# LedGameboardLamp.net
KiCad netlist of a schematic drawn in EasyEDA
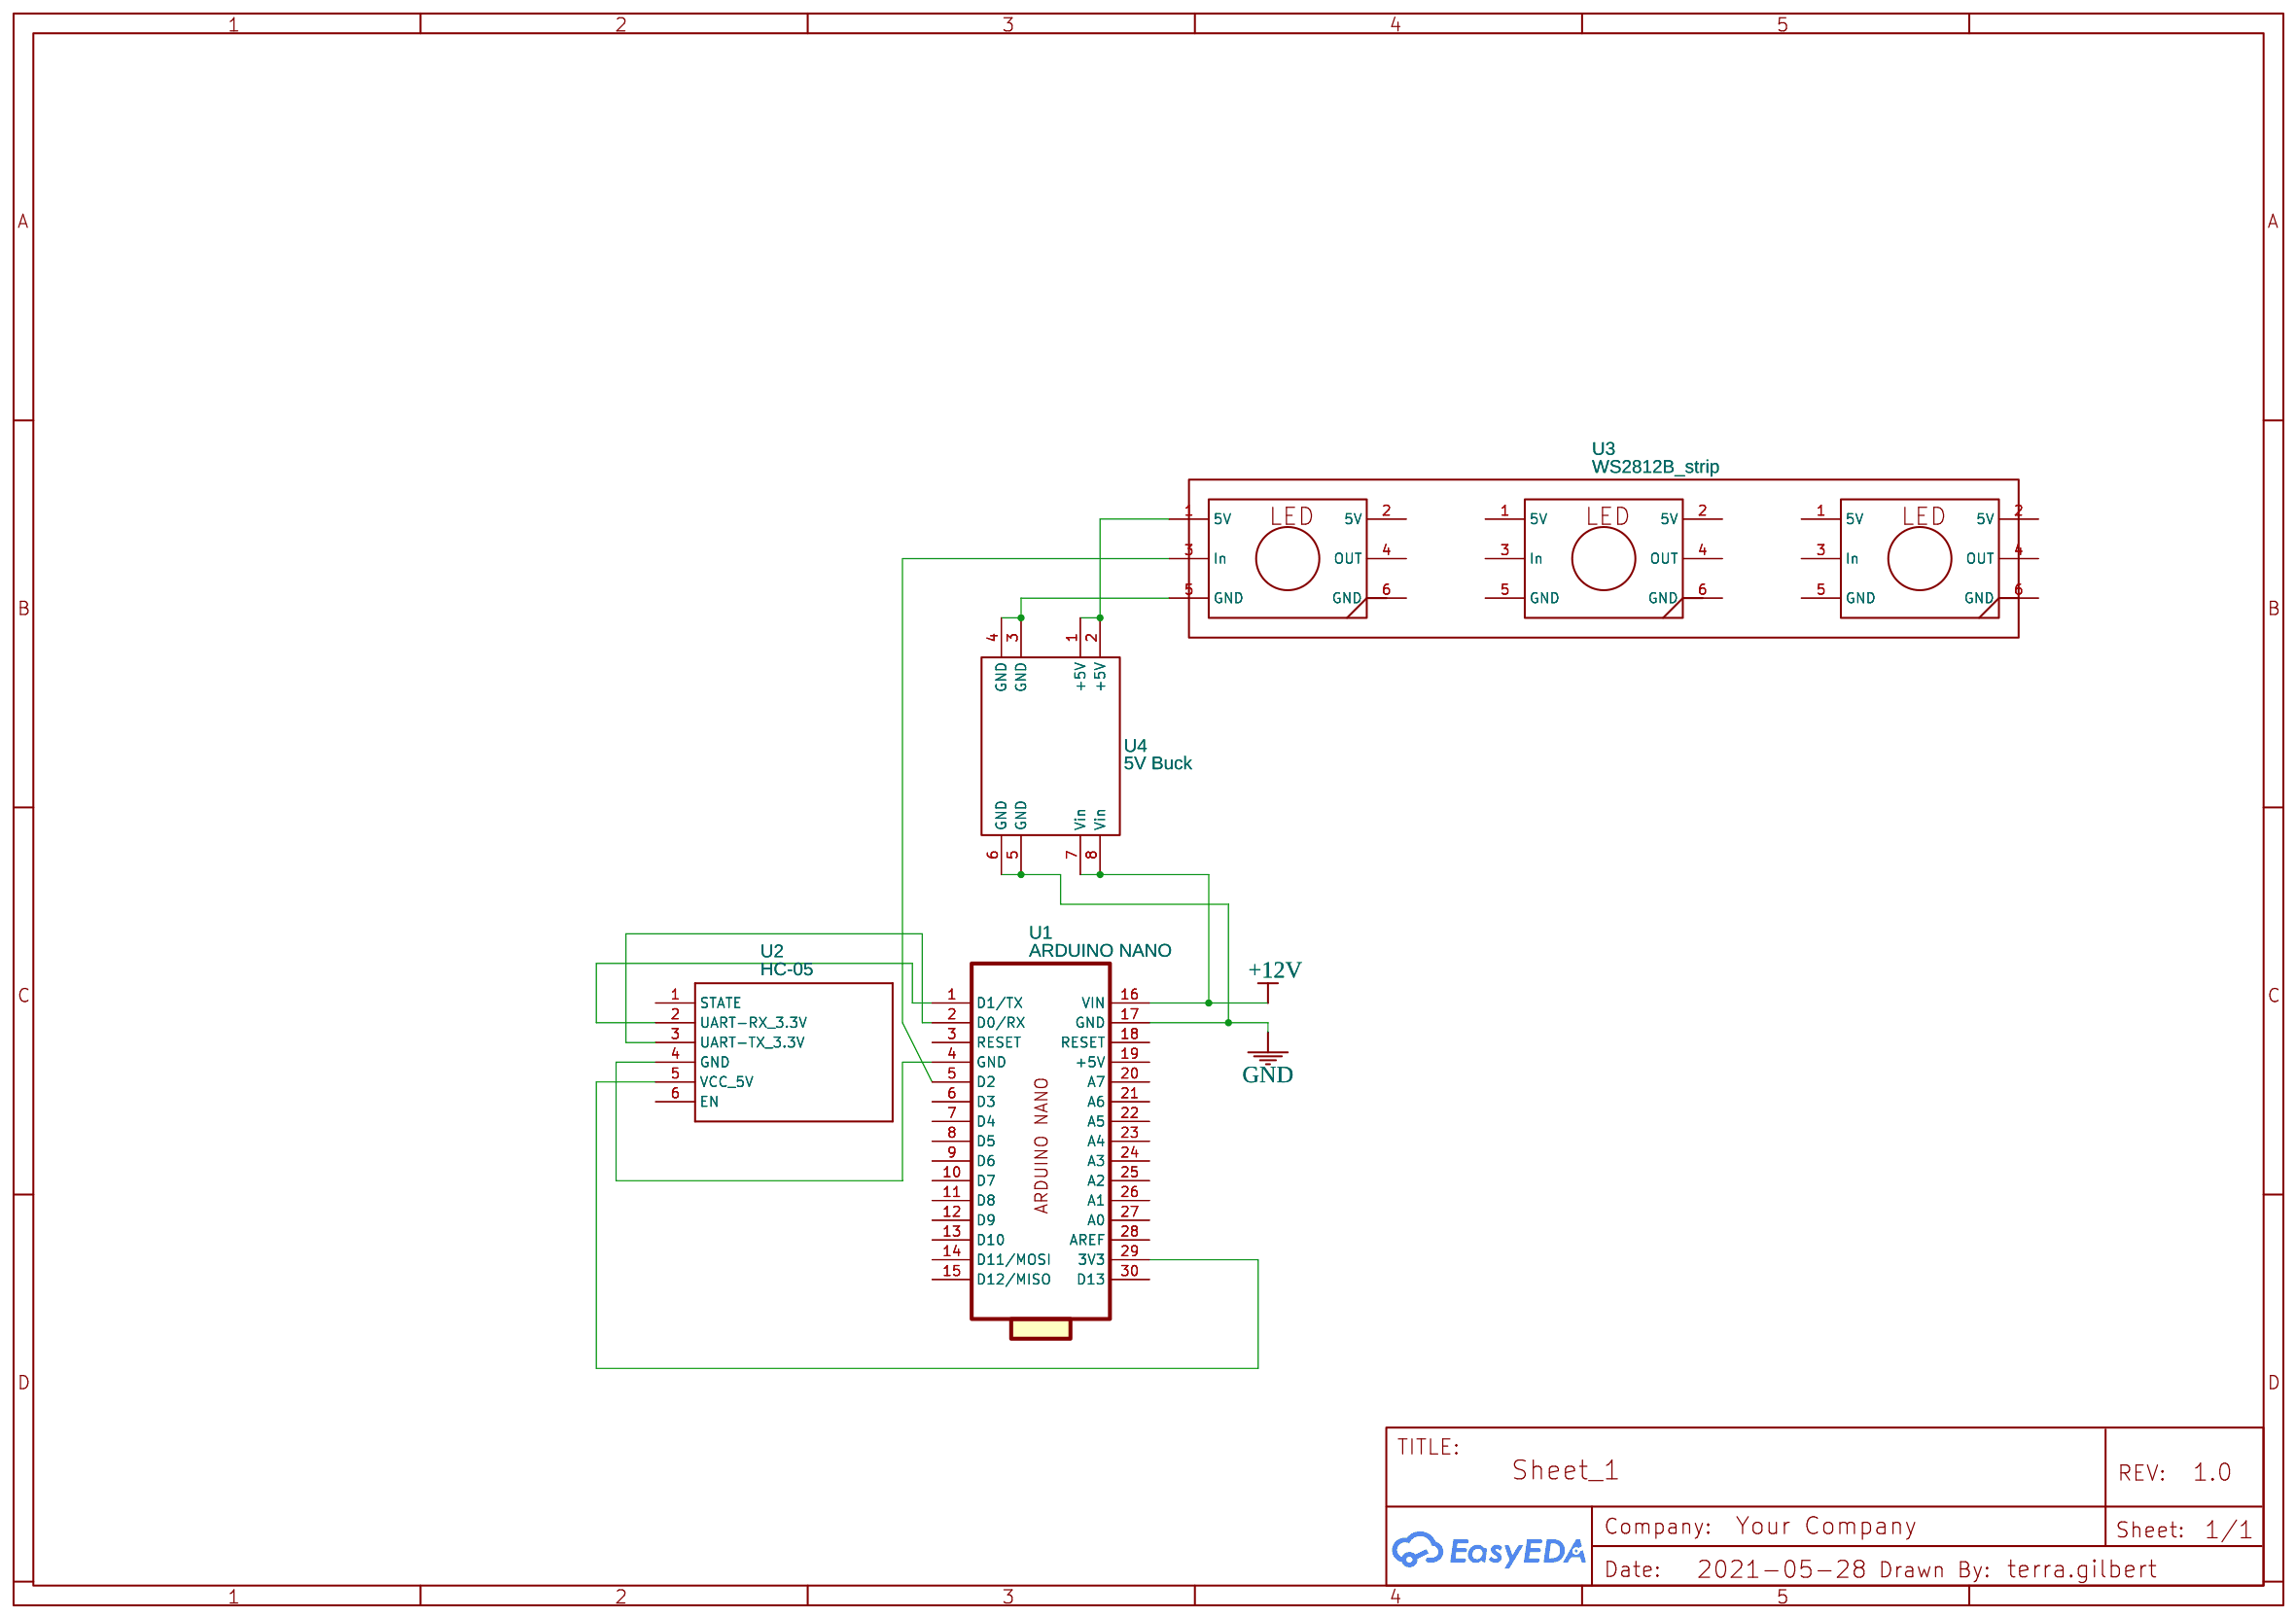
[diagram p0: schematic sheet]

(export (version "E")
  (design (tool "Eeschema 10.0.6"))
  (components
    (comp (ref "U1")
      (value "ARDUINO NANO")
      (fields (field (name "BOM_Manufacturer Part") "arduino nano"))
      (libsource (lib "") (part "ARDUINO NANO"))
    )
    (comp (ref "U2") (value "HC-05") (libsource (lib "") (part "HC-05")))
    (comp (ref "U3") (value "WS2812B_strip") (libsource (lib "") (part "WS2812B_strip")))
    (comp (ref "U4") (value "5V Buck") (libsource (lib "") (part "5V Buck")))
  )
  (nets
    (net (code "1") (name "+12V") (class "Default")
      (node (ref "U1") (pin "16") (pinfunction "VIN_16") (pintype "unspecified"))
      (node (ref "U4") (pin "7") (pinfunction "Vin_7") (pintype "unspecified"))
      (node (ref "U4") (pin "8") (pinfunction "Vin_8") (pintype "unspecified"))
    )
    (net (code "2") (name "GND") (class "Default")
      (node (ref "U1") (pin "17") (pinfunction "GND_17") (pintype "unspecified"))
      (node (ref "U4") (pin "5") (pinfunction "GND_5") (pintype "unspecified"))
      (node (ref "U4") (pin "6") (pinfunction "GND_6") (pintype "unspecified"))
    )
    (net (code "3") (name "Net-(U1-3V3)") (class "Default")
      (node (ref "U1") (pin "29") (pinfunction "3V3_29") (pintype "unspecified"))
      (node (ref "U2") (pin "5") (pinfunction "VCC_5V_5") (pintype "unspecified"))
    )
    (net (code "4") (name "Net-(U1-D0{slash}RX)") (class "Default")
      (node (ref "U1") (pin "2") (pinfunction "D0/RX_2") (pintype "unspecified"))
      (node (ref "U2") (pin "3") (pinfunction "UART-TX_3.3V_3") (pintype "unspecified"))
    )
    (net (code "5") (name "Net-(U1-D1{slash}TX)") (class "Default")
      (node (ref "U1") (pin "1") (pinfunction "D1/TX_1") (pintype "unspecified"))
      (node (ref "U2") (pin "2") (pinfunction "UART-RX_3.3V_2") (pintype "unspecified"))
    )
    (net (code "6") (name "Net-(U1-D2)") (class "Default")
      (node (ref "U1") (pin "5") (pinfunction "D2_5") (pintype "unspecified"))
      (node (ref "U3") (pin "3") (pinfunction "In_3") (pintype "unspecified"))
    )
    (net (code "7") (name "Net-(U2-GND)") (class "Default")
      (node (ref "U1") (pin "4") (pinfunction "GND_4") (pintype "unspecified"))
      (node (ref "U2") (pin "4") (pinfunction "GND_4") (pintype "unspecified"))
    )
    (net (code "8") (name "Net-(U3-5V-Pad1)_1") (class "Default")
      (node (ref "U3") (pin "1") (pinfunction "5V_1") (pintype "unspecified"))
      (node (ref "U4") (pin "1") (pinfunction "+5V_1") (pintype "unspecified"))
      (node (ref "U4") (pin "2") (pinfunction "+5V_2") (pintype "unspecified"))
    )
    (net (code "9") (name "Net-(U3-GND-Pad5)_1") (class "Default")
      (node (ref "U3") (pin "5") (pinfunction "GND_5") (pintype "unspecified"))
      (node (ref "U4") (pin "3") (pinfunction "GND_3") (pintype "unspecified"))
      (node (ref "U4") (pin "4") (pinfunction "GND_4") (pintype "unspecified"))
    )
    (net (code "10") (name "unconnected-(U1-+5V-Pad19)") (class "Default")
      (node (ref "U1") (pin "19") (pinfunction "+5V_19") (pintype "unspecified"))
    )
    (net (code "11") (name "unconnected-(U1-A0-Pad27)") (class "Default")
      (node (ref "U1") (pin "27") (pinfunction "A0_27") (pintype "unspecified"))
    )
    (net (code "12") (name "unconnected-(U1-A1-Pad26)") (class "Default")
      (node (ref "U1") (pin "26") (pinfunction "A1_26") (pintype "unspecified"))
    )
    (net (code "13") (name "unconnected-(U1-A2-Pad25)") (class "Default")
      (node (ref "U1") (pin "25") (pinfunction "A2_25") (pintype "unspecified"))
    )
    (net (code "14") (name "unconnected-(U1-A3-Pad24)") (class "Default")
      (node (ref "U1") (pin "24") (pinfunction "A3_24") (pintype "unspecified"))
    )
    (net (code "15") (name "unconnected-(U1-A4-Pad23)") (class "Default")
      (node (ref "U1") (pin "23") (pinfunction "A4_23") (pintype "unspecified"))
    )
    (net (code "16") (name "unconnected-(U1-A5-Pad22)") (class "Default")
      (node (ref "U1") (pin "22") (pinfunction "A5_22") (pintype "unspecified"))
    )
    (net (code "17") (name "unconnected-(U1-A6-Pad21)") (class "Default")
      (node (ref "U1") (pin "21") (pinfunction "A6_21") (pintype "unspecified"))
    )
    (net (code "18") (name "unconnected-(U1-A7-Pad20)") (class "Default")
      (node (ref "U1") (pin "20") (pinfunction "A7_20") (pintype "unspecified"))
    )
    (net (code "19") (name "unconnected-(U1-AREF-Pad28)") (class "Default")
      (node (ref "U1") (pin "28") (pinfunction "AREF_28") (pintype "unspecified"))
    )
    (net (code "20") (name "unconnected-(U1-D3-Pad6)") (class "Default")
      (node (ref "U1") (pin "6") (pinfunction "D3_6") (pintype "unspecified"))
    )
    (net (code "21") (name "unconnected-(U1-D4-Pad7)") (class "Default")
      (node (ref "U1") (pin "7") (pinfunction "D4_7") (pintype "unspecified"))
    )
    (net (code "22") (name "unconnected-(U1-D5-Pad8)") (class "Default")
      (node (ref "U1") (pin "8") (pinfunction "D5_8") (pintype "unspecified"))
    )
    (net (code "23") (name "unconnected-(U1-D6-Pad9)") (class "Default")
      (node (ref "U1") (pin "9") (pinfunction "D6_9") (pintype "unspecified"))
    )
    (net (code "24") (name "unconnected-(U1-D7-Pad10)") (class "Default")
      (node (ref "U1") (pin "10") (pinfunction "D7_10") (pintype "unspecified"))
    )
    (net (code "25") (name "unconnected-(U1-D8-Pad11)") (class "Default")
      (node (ref "U1") (pin "11") (pinfunction "D8_11") (pintype "unspecified"))
    )
    (net (code "26") (name "unconnected-(U1-D9-Pad12)") (class "Default")
      (node (ref "U1") (pin "12") (pinfunction "D9_12") (pintype "unspecified"))
    )
    (net (code "27") (name "unconnected-(U1-D10-Pad13)") (class "Default")
      (node (ref "U1") (pin "13") (pinfunction "D10_13") (pintype "unspecified"))
    )
    (net (code "28") (name "unconnected-(U1-D11{slash}MOSI-Pad14)") (class "Default")
      (node (ref "U1") (pin "14") (pinfunction "D11/MOSI_14") (pintype "unspecified"))
    )
    (net (code "29") (name "unconnected-(U1-D12{slash}MISO-Pad15)") (class "Default")
      (node (ref "U1") (pin "15") (pinfunction "D12/MISO_15") (pintype "unspecified"))
    )
    (net (code "30") (name "unconnected-(U1-D13-Pad30)") (class "Default")
      (node (ref "U1") (pin "30") (pinfunction "D13_30") (pintype "unspecified"))
    )
    (net (code "31") (name "unconnected-(U1-RESET-Pad3)") (class "Default")
      (node (ref "U1") (pin "3") (pinfunction "RESET_3") (pintype "unspecified"))
    )
    (net (code "32") (name "unconnected-(U1-RESET-Pad18)") (class "Default")
      (node (ref "U1") (pin "18") (pinfunction "RESET_18") (pintype "unspecified"))
    )
    (net (code "33") (name "unconnected-(U2-EN-Pad6)") (class "Default")
      (node (ref "U2") (pin "6") (pinfunction "EN_6") (pintype "unspecified"))
    )
    (net (code "34") (name "unconnected-(U2-STATE-Pad1)") (class "Default")
      (node (ref "U2") (pin "1") (pinfunction "STATE_1") (pintype "unspecified"))
    )
    (net (code "35") (name "unconnected-(U3-5V-Pad1)") (class "Default")
      (node (ref "U3") (pin "1") (pinfunction "5V_1") (pintype "unspecified"))
    )
    (net (code "36") (name "unconnected-(U3-5V-Pad1)_2") (class "Default")
      (node (ref "U3") (pin "1") (pinfunction "5V_1") (pintype "unspecified"))
    )
    (net (code "37") (name "unconnected-(U3-5V-Pad2)") (class "Default")
      (node (ref "U3") (pin "2") (pinfunction "5V_2") (pintype "unspecified"))
    )
    (net (code "38") (name "unconnected-(U3-5V-Pad2)_1") (class "Default")
      (node (ref "U3") (pin "2") (pinfunction "5V_2") (pintype "unspecified"))
    )
    (net (code "39") (name "unconnected-(U3-5V-Pad2)_2") (class "Default")
      (node (ref "U3") (pin "2") (pinfunction "5V_2") (pintype "unspecified"))
    )
    (net (code "40") (name "unconnected-(U3-GND-Pad5)") (class "Default")
      (node (ref "U3") (pin "5") (pinfunction "GND_5") (pintype "unspecified"))
    )
    (net (code "41") (name "unconnected-(U3-GND-Pad5)_2") (class "Default")
      (node (ref "U3") (pin "5") (pinfunction "GND_5") (pintype "unspecified"))
    )
    (net (code "42") (name "unconnected-(U3-GND-Pad6)") (class "Default")
      (node (ref "U3") (pin "6") (pinfunction "GND_6") (pintype "unspecified"))
    )
    (net (code "43") (name "unconnected-(U3-GND-Pad6)_1") (class "Default")
      (node (ref "U3") (pin "6") (pinfunction "GND_6") (pintype "unspecified"))
    )
    (net (code "44") (name "unconnected-(U3-GND-Pad6)_2") (class "Default")
      (node (ref "U3") (pin "6") (pinfunction "GND_6") (pintype "unspecified"))
    )
    (net (code "45") (name "unconnected-(U3-In-Pad3)") (class "Default")
      (node (ref "U3") (pin "3") (pinfunction "In_3") (pintype "unspecified"))
    )
    (net (code "46") (name "unconnected-(U3-In-Pad3)_1") (class "Default")
      (node (ref "U3") (pin "3") (pinfunction "In_3") (pintype "unspecified"))
    )
    (net (code "47") (name "unconnected-(U3-OUT-Pad4)") (class "Default")
      (node (ref "U3") (pin "4") (pinfunction "OUT_4") (pintype "unspecified"))
    )
    (net (code "48") (name "unconnected-(U3-OUT-Pad4)_1") (class "Default")
      (node (ref "U3") (pin "4") (pinfunction "OUT_4") (pintype "unspecified"))
    )
    (net (code "49") (name "unconnected-(U3-OUT-Pad4)_2") (class "Default")
      (node (ref "U3") (pin "4") (pinfunction "OUT_4") (pintype "unspecified"))
    )
  )
)
